# aq_mx_v1-6-0a.net
KiCad netlist of a schematic drawn in EAGLE
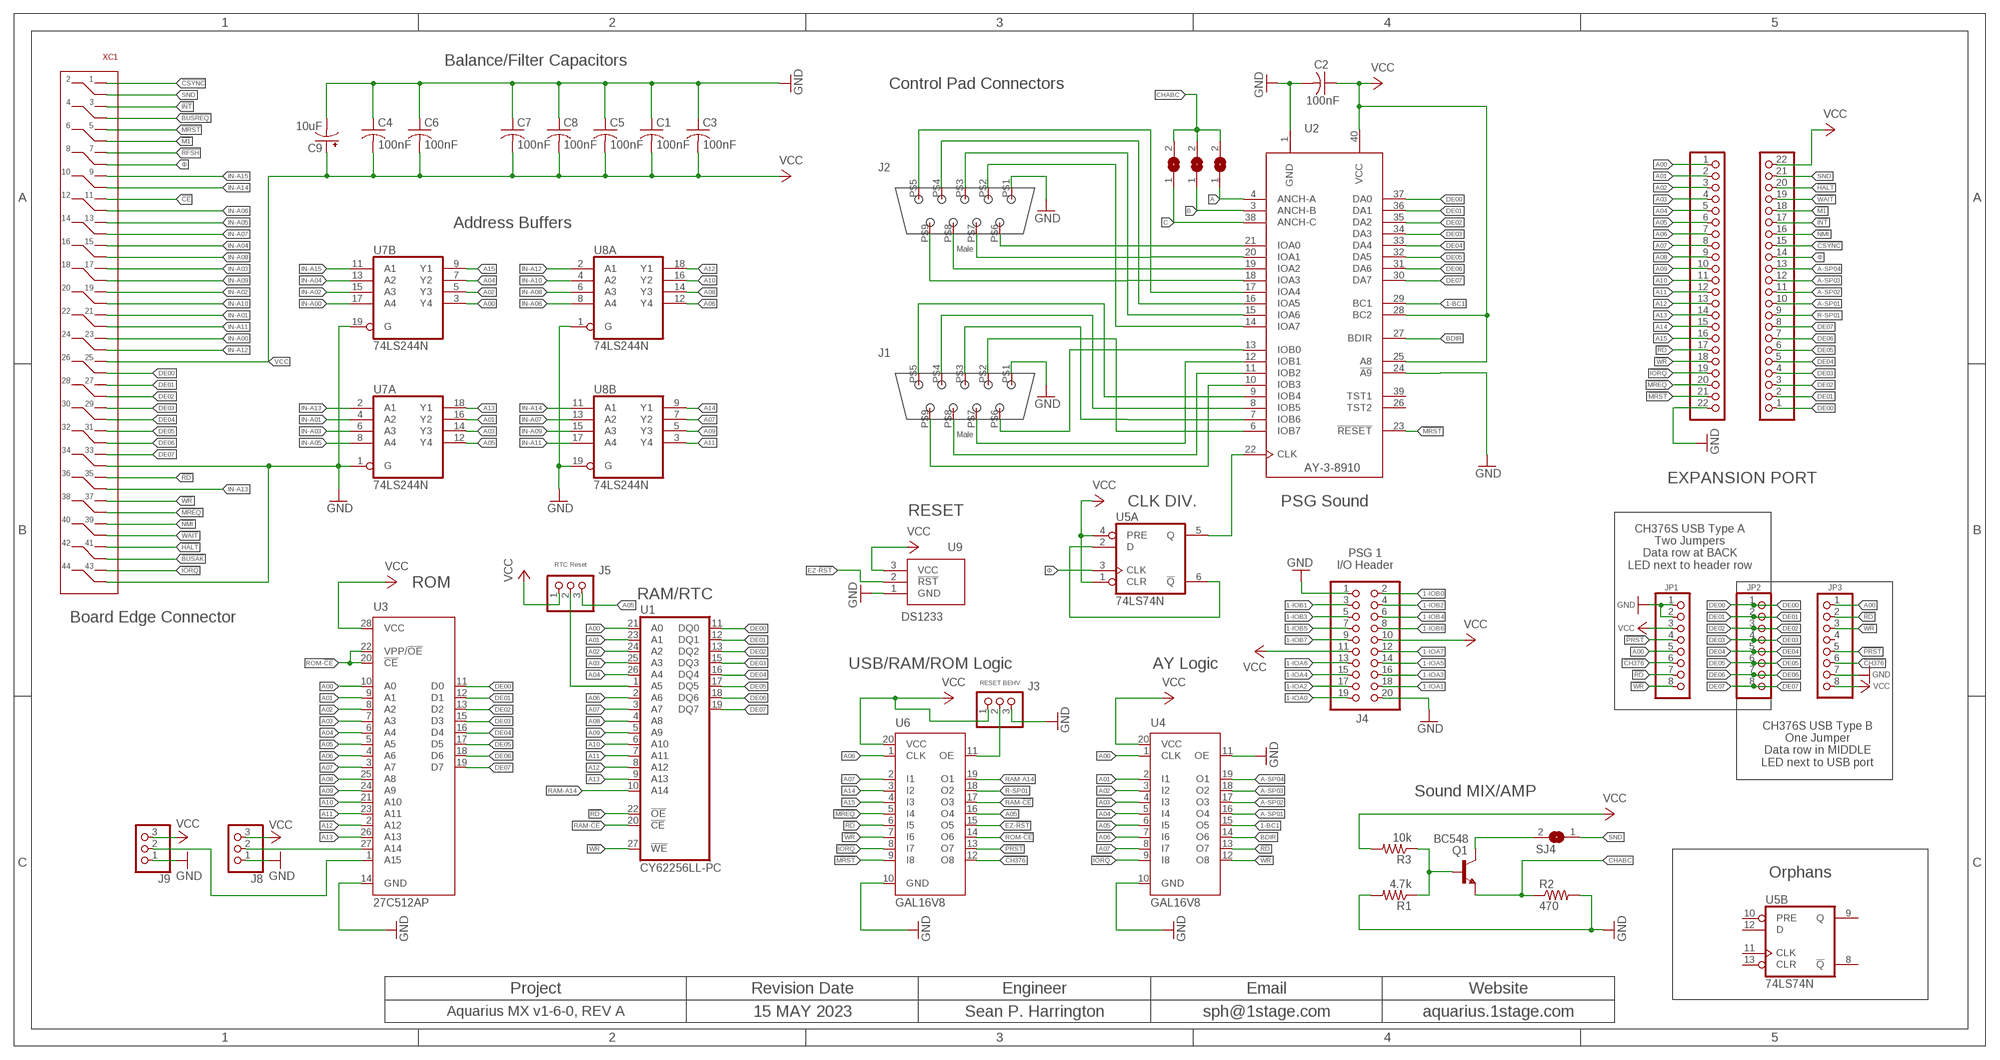
[diagram p0: schematic, sheet 1]

(export (version "E")
  (design (tool "Eeschema 10.0.6"))
  (components
    (comp (ref "C1")
      (value "100nF")
      (footprint "eagle-import:C050-025X075")
      (libsource (lib "eagle-import") (part "C-US050-025X075"))
    )
    (comp (ref "C2")
      (value "100nF")
      (footprint "eagle-import:C050-025X075")
      (libsource (lib "eagle-import") (part "C-US050-025X075"))
    )
    (comp (ref "C3")
      (value "100nF")
      (footprint "eagle-import:C050-025X075")
      (libsource (lib "eagle-import") (part "C-US050-025X075"))
    )
    (comp (ref "C4")
      (value "100nF")
      (footprint "eagle-import:C050-025X075")
      (libsource (lib "eagle-import") (part "C-US050-025X075"))
    )
    (comp (ref "C5")
      (value "100nF")
      (footprint "eagle-import:C050-025X075")
      (libsource (lib "eagle-import") (part "C-US050-025X075"))
    )
    (comp (ref "C6")
      (value "100nF")
      (footprint "eagle-import:C050-025X075")
      (libsource (lib "eagle-import") (part "C-US050-025X075"))
    )
    (comp (ref "C7")
      (value "100nF")
      (footprint "eagle-import:C050-025X075")
      (libsource (lib "eagle-import") (part "C-US050-025X075"))
    )
    (comp (ref "C8")
      (value "100nF")
      (footprint "eagle-import:C050-025X075")
      (libsource (lib "eagle-import") (part "C-US050-025X075"))
    )
    (comp (ref "C9")
      (value "10uF")
      (footprint "eagle-import:E22-6")
      (libsource (lib "eagle-import") (part "CPOL-USE22-6AXIAL"))
    )
    (comp (ref "J1")
      (value "DB9-MALE-RA")
      (footprint "eagle-import:DB9-MALE-RA")
      (libsource (lib "eagle-import") (part "DB9-MALE-RA"))
    )
    (comp (ref "J2")
      (value "DB9-MALE-RA")
      (footprint "eagle-import:DB9-MALE-RA")
      (libsource (lib "eagle-import") (part "DB9-MALE-RA"))
    )
    (comp (ref "J3")
      (value "RESET BEHV.")
      (footprint "eagle-import:1X03")
      (libsource (lib "eagle-import") (part "PINHD-1X3"))
    )
    (comp (ref "J4")
      (value "PINHD-2X10")
      (footprint "eagle-import:2X10")
      (libsource (lib "eagle-import") (part "PINHD-2X10"))
    )
    (comp (ref "J5")
      (value "RTC Reset")
      (footprint "eagle-import:1X03")
      (libsource (lib "eagle-import") (part "PINHD-1X3"))
    )
    (comp (ref "J6")
      (value "PINHD-1X22")
      (footprint "eagle-import:1X22")
      (libsource (lib "eagle-import") (part "PINHD-1X22"))
    )
    (comp (ref "J7")
      (value "PINHD-1X22")
      (footprint "eagle-import:1X22")
      (libsource (lib "eagle-import") (part "PINHD-1X22"))
    )
    (comp (ref "J8")
      (value "PINHD-1X3")
      (footprint "eagle-import:1X03")
      (libsource (lib "eagle-import") (part "PINHD-1X3"))
    )
    (comp (ref "J9")
      (value "PINHD-1X3")
      (footprint "eagle-import:1X03")
      (libsource (lib "eagle-import") (part "PINHD-1X3"))
    )
    (comp (ref "JP1")
      (value "PINHD-1X8")
      (footprint "eagle-import:1X08")
      (libsource (lib "eagle-import") (part "PINHD-1X8"))
    )
    (comp (ref "JP2")
      (value "PINHD-1X8")
      (footprint "eagle-import:1X08")
      (libsource (lib "eagle-import") (part "PINHD-1X8"))
    )
    (comp (ref "JP3")
      (value "PINHD-1X8")
      (footprint "eagle-import:1X08")
      (libsource (lib "eagle-import") (part "PINHD-1X8"))
    )
    (comp (ref "Q1")
      (value "BC548")
      (footprint "eagle-import:TO92-CBE")
      (libsource (lib "eagle-import") (part "-NPN-TO92-CBEBC548"))
    )
    (comp (ref "R1")
      (value "4.7k")
      (footprint "eagle-import:0204_7")
      (libsource (lib "eagle-import") (part "R-US_0204/7"))
    )
    (comp (ref "R2")
      (value "470")
      (footprint "eagle-import:0204_7")
      (libsource (lib "eagle-import") (part "R-US_0204/7"))
    )
    (comp (ref "R3")
      (value "10k")
      (footprint "eagle-import:0204_7")
      (libsource (lib "eagle-import") (part "R-US_0204/7"))
    )
    (comp (ref "SJ1") (value "SJ") (footprint "eagle-import:SJ") (libsource (lib "eagle-import") (part "SJ")))
    (comp (ref "SJ2") (value "SJ") (footprint "eagle-import:SJ") (libsource (lib "eagle-import") (part "SJ")))
    (comp (ref "SJ3") (value "SJ") (footprint "eagle-import:SJ") (libsource (lib "eagle-import") (part "SJ")))
    (comp (ref "SJ4") (value "SJ") (footprint "eagle-import:SJ") (libsource (lib "eagle-import") (part "SJ")))
    (comp (ref "U1")
      (value "CY62256LL-PC")
      (footprint "eagle-import:DIL28-6")
      (libsource (lib "eagle-import") (part "CY62256LL-?PC"))
    )
    (comp (ref "U2")
      (value "AY-3-8910")
      (footprint "eagle-import:RAD38910-DIL40-6")
      (libsource (lib "eagle-import") (part "RAD38910DIL40-6"))
    )
    (comp (ref "U3")
      (value "27C512AP")
      (footprint "eagle-import:DIL28-6")
      (fields (field (name "MPN") "M27C512-90B6"))
      (libsource (lib "eagle-import") (part "27512APC"))
    )
    (comp (ref "U4")
      (value "GAL16V8")
      (footprint "eagle-import:DIL20")
      (fields (field (name "MPN") "ATF16V8CZ-15PU"))
      (libsource (lib "eagle-import") (part "ATF16V8BP3"))
    )
    (comp (ref "U5")
      (value "74LS74N")
      (footprint "eagle-import:DIL14")
      (libsource (lib "eagle-import") (part "7474NLS"))
    )
    (comp (ref "U6")
      (value "GAL16V8")
      (footprint "eagle-import:DIL20")
      (fields (field (name "MPN") "ATF16V8CZ-15PU"))
      (libsource (lib "eagle-import") (part "ATF16V8BP3"))
    )
    (comp (ref "U7")
      (value "74LS244N")
      (footprint "eagle-import:DIL20")
      (libsource (lib "eagle-import") (part "74244NLS"))
    )
    (comp (ref "U8")
      (value "74LS244N")
      (footprint "eagle-import:DIL20")
      (libsource (lib "eagle-import") (part "74244NLS"))
    )
    (comp (ref "U9")
      (value "DS1233")
      (footprint "eagle-import:TO-92")
      (fields
        (field (name "ARROW_PART_NUMBER") "DS1233-10+")
        (field (name "MOUSER_PART_NUMBER") "700-DS1233-10")
      )
      (libsource (lib "eagle-import") (part "DS1233-10+"))
    )
    (comp (ref "XC1")
      (value "AQ-CART-EDGE")
      (footprint "eagle-import:AQ-CART-EDGE")
      (libsource (lib "eagle-import") (part "AQ-CART-EDGE"))
    )
  )
  (nets
    (net (code "1") (name "/EZ-~{RST}") (class "Default")
      (node (ref "U6") (pin "15") (pinfunction "O5_15") (pintype "output"))
      (node (ref "U9") (pin "2") (pinfunction "~{RST}_2") (pintype "input"))
    )
    (net (code "2") (name "/RAM-~{CE}") (class "Default")
      (node (ref "U1") (pin "20") (pinfunction "~{CE}_20") (pintype "input"))
      (node (ref "U6") (pin "17") (pinfunction "O3_17") (pintype "output"))
    )
    (net (code "3") (name "/ROM-~{CE}") (class "Default")
      (node (ref "U3") (pin "20") (pinfunction "~{CE}_20") (pintype "input"))
      (node (ref "U3") (pin "22") (pinfunction "VPP/~{OE}_22") (pintype "input"))
      (node (ref "U6") (pin "14") (pinfunction "O6_14") (pintype "output"))
    )
    (net (code "4") (name "/~{BUSAK}") (class "Default")
      (node (ref "XC1") (pin "P$42") (pinfunction "X42_P$42") (pintype "bidirectional"))
    )
    (net (code "5") (name "/~{BUSREQ}") (class "Default")
      (node (ref "XC1") (pin "P$4") (pinfunction "X4_P$4") (pintype "bidirectional"))
    )
    (net (code "6") (name "/~{CE}") (class "Default")
      (node (ref "XC1") (pin "P$11") (pinfunction "X11_P$11") (pintype "bidirectional"))
    )
    (net (code "7") (name "/~{CH376}") (class "Default")
      (node (ref "JP1") (pin "6") (pinfunction "6_6") (pintype "passive"))
      (node (ref "JP3") (pin "6") (pinfunction "6_6") (pintype "passive"))
      (node (ref "U6") (pin "12") (pinfunction "O8_12") (pintype "output"))
    )
    (net (code "8") (name "/~{CSYNC}") (class "Default")
      (node (ref "J6") (pin "15") (pinfunction "15_15") (pintype "passive"))
      (node (ref "XC1") (pin "P$1") (pinfunction "X1_P$1") (pintype "bidirectional"))
    )
    (net (code "9") (name "/~{HALT}") (class "Default")
      (node (ref "J6") (pin "20") (pinfunction "20_20") (pintype "passive"))
      (node (ref "XC1") (pin "P$41") (pinfunction "X41_P$41") (pintype "bidirectional"))
    )
    (net (code "10") (name "/~{INT}") (class "Default")
      (node (ref "J6") (pin "17") (pinfunction "17_17") (pintype "passive"))
      (node (ref "XC1") (pin "P$3") (pinfunction "X3_P$3") (pintype "bidirectional"))
    )
    (net (code "11") (name "/~{IORQ}") (class "Default")
      (node (ref "J7") (pin "19") (pinfunction "19_19") (pintype "passive"))
      (node (ref "U4") (pin "9") (pinfunction "I8_9") (pintype "input"))
      (node (ref "U6") (pin "8") (pinfunction "I7_8") (pintype "input"))
      (node (ref "XC1") (pin "P$43") (pinfunction "X43_P$43") (pintype "bidirectional"))
    )
    (net (code "12") (name "/~{M1}") (class "Default")
      (node (ref "J6") (pin "18") (pinfunction "18_18") (pintype "passive"))
      (node (ref "XC1") (pin "P$6") (pinfunction "X6_P$6") (pintype "bidirectional"))
    )
    (net (code "13") (name "/~{MREQ}") (class "Default")
      (node (ref "J7") (pin "20") (pinfunction "20_20") (pintype "passive"))
      (node (ref "U6") (pin "5") (pinfunction "I4_5") (pintype "input"))
      (node (ref "XC1") (pin "P$38") (pinfunction "X38_P$38") (pintype "bidirectional"))
    )
    (net (code "14") (name "/~{MRST}") (class "Default")
      (node (ref "J7") (pin "21") (pinfunction "21_21") (pintype "passive"))
      (node (ref "U2") (pin "23") (pinfunction "~{RESET}_23") (pintype "bidirectional"))
      (node (ref "U6") (pin "9") (pinfunction "I8_9") (pintype "input"))
      (node (ref "XC1") (pin "P$5") (pinfunction "X5_P$5") (pintype "bidirectional"))
    )
    (net (code "15") (name "/~{NMI}") (class "Default")
      (node (ref "J6") (pin "16") (pinfunction "16_16") (pintype "passive"))
      (node (ref "XC1") (pin "P$39") (pinfunction "X39_P$39") (pintype "bidirectional"))
    )
    (net (code "16") (name "/~{PRST}") (class "Default")
      (node (ref "JP1") (pin "4") (pinfunction "4_4") (pintype "passive"))
      (node (ref "JP3") (pin "5") (pinfunction "5_5") (pintype "passive"))
      (node (ref "U6") (pin "13") (pinfunction "O7_13") (pintype "output"))
    )
    (net (code "17") (name "/~{RD}") (class "Default")
      (node (ref "J7") (pin "17") (pinfunction "17_17") (pintype "passive"))
      (node (ref "JP1") (pin "7") (pinfunction "7_7") (pintype "passive"))
      (node (ref "JP3") (pin "2") (pinfunction "2_2") (pintype "passive"))
      (node (ref "U1") (pin "22") (pinfunction "~{OE}_22") (pintype "input"))
      (node (ref "U4") (pin "13") (pinfunction "O7_13") (pintype "output"))
      (node (ref "U6") (pin "6") (pinfunction "I5_6") (pintype "input"))
      (node (ref "XC1") (pin "P$35") (pinfunction "X35_P$35") (pintype "bidirectional"))
    )
    (net (code "18") (name "/~{RFSH}") (class "Default")
      (node (ref "XC1") (pin "P$7") (pinfunction "X7_P$7") (pintype "bidirectional"))
    )
    (net (code "19") (name "/~{WAIT}") (class "Default")
      (node (ref "J6") (pin "19") (pinfunction "19_19") (pintype "passive"))
      (node (ref "XC1") (pin "P$40") (pinfunction "X40_P$40") (pintype "bidirectional"))
    )
    (net (code "20") (name "/~{WR}") (class "Default")
      (node (ref "J7") (pin "18") (pinfunction "18_18") (pintype "passive"))
      (node (ref "JP1") (pin "8") (pinfunction "8_8") (pintype "passive"))
      (node (ref "JP3") (pin "3") (pinfunction "3_3") (pintype "passive"))
      (node (ref "U1") (pin "27") (pinfunction "~{WE}_27") (pintype "input"))
      (node (ref "U4") (pin "12") (pinfunction "O8_12") (pintype "output"))
      (node (ref "U6") (pin "7") (pinfunction "I6_7") (pintype "input"))
      (node (ref "XC1") (pin "P$37") (pinfunction "X37_P$37") (pintype "bidirectional"))
    )
    (net (code "21") (name "1-BC1") (class "Default")
      (node (ref "U2") (pin "29") (pinfunction "BC1_29") (pintype "bidirectional"))
      (node (ref "U4") (pin "15") (pinfunction "O5_15") (pintype "output"))
    )
    (net (code "22") (name "1-IOA0") (class "Default")
      (node (ref "J2") (pin "P$6") (pinfunction "P$6_P$6") (pintype "bidirectional"))
      (node (ref "J4") (pin "19") (pinfunction "19_19") (pintype "passive"))
      (node (ref "U2") (pin "21") (pinfunction "IOA0_21") (pintype "bidirectional"))
    )
    (net (code "23") (name "1-IOA1") (class "Default")
      (node (ref "J2") (pin "P$7") (pinfunction "P$7_P$7") (pintype "bidirectional"))
      (node (ref "J4") (pin "18") (pinfunction "18_18") (pintype "passive"))
      (node (ref "U2") (pin "20") (pinfunction "IOA1_20") (pintype "bidirectional"))
    )
    (net (code "24") (name "1-IOA2") (class "Default")
      (node (ref "J2") (pin "P$8") (pinfunction "P$8_P$8") (pintype "bidirectional"))
      (node (ref "J4") (pin "17") (pinfunction "17_17") (pintype "passive"))
      (node (ref "U2") (pin "19") (pinfunction "IOA2_19") (pintype "bidirectional"))
    )
    (net (code "25") (name "1-IOA3") (class "Default")
      (node (ref "J2") (pin "P$9") (pinfunction "P$9_P$9") (pintype "bidirectional"))
      (node (ref "J4") (pin "16") (pinfunction "16_16") (pintype "passive"))
      (node (ref "U2") (pin "18") (pinfunction "IOA3_18") (pintype "bidirectional"))
    )
    (net (code "26") (name "1-IOA4") (class "Default")
      (node (ref "J2") (pin "P$5") (pinfunction "P$5_P$5") (pintype "bidirectional"))
      (node (ref "J4") (pin "15") (pinfunction "15_15") (pintype "passive"))
      (node (ref "U2") (pin "17") (pinfunction "IOA4_17") (pintype "bidirectional"))
    )
    (net (code "27") (name "1-IOA5") (class "Default")
      (node (ref "J2") (pin "P$4") (pinfunction "P$4_P$4") (pintype "bidirectional"))
      (node (ref "J4") (pin "14") (pinfunction "14_14") (pintype "passive"))
      (node (ref "U2") (pin "16") (pinfunction "IOA5_16") (pintype "bidirectional"))
    )
    (net (code "28") (name "1-IOA6") (class "Default")
      (node (ref "J2") (pin "P$3") (pinfunction "P$3_P$3") (pintype "bidirectional"))
      (node (ref "J4") (pin "13") (pinfunction "13_13") (pintype "passive"))
      (node (ref "U2") (pin "15") (pinfunction "IOA6_15") (pintype "bidirectional"))
    )
    (net (code "29") (name "1-IOA7") (class "Default")
      (node (ref "J2") (pin "P$2") (pinfunction "P$2_P$2") (pintype "bidirectional"))
      (node (ref "J4") (pin "12") (pinfunction "12_12") (pintype "passive"))
      (node (ref "U2") (pin "14") (pinfunction "IOA7_14") (pintype "bidirectional"))
    )
    (net (code "30") (name "1-IOB0") (class "Default")
      (node (ref "J1") (pin "P$6") (pinfunction "P$6_P$6") (pintype "bidirectional"))
      (node (ref "J4") (pin "2") (pinfunction "2_2") (pintype "passive"))
      (node (ref "U2") (pin "13") (pinfunction "IOB0_13") (pintype "bidirectional"))
    )
    (net (code "31") (name "1-IOB1") (class "Default")
      (node (ref "J1") (pin "P$7") (pinfunction "P$7_P$7") (pintype "bidirectional"))
      (node (ref "J4") (pin "3") (pinfunction "3_3") (pintype "passive"))
      (node (ref "U2") (pin "12") (pinfunction "IOB1_12") (pintype "bidirectional"))
    )
    (net (code "32") (name "1-IOB2") (class "Default")
      (node (ref "J1") (pin "P$8") (pinfunction "P$8_P$8") (pintype "bidirectional"))
      (node (ref "J4") (pin "4") (pinfunction "4_4") (pintype "passive"))
      (node (ref "U2") (pin "11") (pinfunction "IOB2_11") (pintype "bidirectional"))
    )
    (net (code "33") (name "1-IOB3") (class "Default")
      (node (ref "J1") (pin "P$9") (pinfunction "P$9_P$9") (pintype "bidirectional"))
      (node (ref "J4") (pin "5") (pinfunction "5_5") (pintype "passive"))
      (node (ref "U2") (pin "10") (pinfunction "IOB3_10") (pintype "bidirectional"))
    )
    (net (code "34") (name "1-IOB4") (class "Default")
      (node (ref "J1") (pin "P$5") (pinfunction "P$5_P$5") (pintype "bidirectional"))
      (node (ref "J4") (pin "6") (pinfunction "6_6") (pintype "passive"))
      (node (ref "U2") (pin "9") (pinfunction "IOB4_9") (pintype "bidirectional"))
    )
    (net (code "35") (name "1-IOB5") (class "Default")
      (node (ref "J1") (pin "P$4") (pinfunction "P$4_P$4") (pintype "bidirectional"))
      (node (ref "J4") (pin "7") (pinfunction "7_7") (pintype "passive"))
      (node (ref "U2") (pin "8") (pinfunction "IOB5_8") (pintype "bidirectional"))
    )
    (net (code "36") (name "1-IOB6") (class "Default")
      (node (ref "J1") (pin "P$3") (pinfunction "P$3_P$3") (pintype "bidirectional"))
      (node (ref "J4") (pin "8") (pinfunction "8_8") (pintype "passive"))
      (node (ref "U2") (pin "7") (pinfunction "IOB6_7") (pintype "bidirectional"))
    )
    (net (code "37") (name "1-IOB7") (class "Default")
      (node (ref "J1") (pin "P$2") (pinfunction "P$2_P$2") (pintype "bidirectional"))
      (node (ref "J4") (pin "9") (pinfunction "9_9") (pintype "passive"))
      (node (ref "U2") (pin "6") (pinfunction "IOB7_6") (pintype "bidirectional"))
    )
    (net (code "38") (name "A") (class "Default")
      (node (ref "SJ1") (pin "1") (pinfunction "1_1") (pintype "passive"))
      (node (ref "U2") (pin "4") (pinfunction "ANCH-A_4") (pintype "bidirectional"))
    )
    (net (code "39") (name "A-SP01") (class "Default")
      (node (ref "J6") (pin "10") (pinfunction "10_10") (pintype "passive"))
      (node (ref "U4") (pin "16") (pinfunction "O4_16") (pintype "output"))
    )
    (net (code "40") (name "A-SP02") (class "Default")
      (node (ref "J6") (pin "11") (pinfunction "11_11") (pintype "passive"))
      (node (ref "U4") (pin "17") (pinfunction "O3_17") (pintype "output"))
    )
    (net (code "41") (name "A-SP03") (class "Default")
      (node (ref "J6") (pin "12") (pinfunction "12_12") (pintype "passive"))
      (node (ref "U4") (pin "18") (pinfunction "O2_18") (pintype "output"))
    )
    (net (code "42") (name "A-SP04") (class "Default")
      (node (ref "J6") (pin "13") (pinfunction "13_13") (pintype "passive"))
      (node (ref "U4") (pin "19") (pinfunction "O1_19") (pintype "output"))
    )
    (net (code "43") (name "A00") (class "Default")
      (node (ref "J7") (pin "1") (pinfunction "1_1") (pintype "passive"))
      (node (ref "JP1") (pin "5") (pinfunction "5_5") (pintype "passive"))
      (node (ref "JP3") (pin "1") (pinfunction "1_1") (pintype "passive"))
      (node (ref "U1") (pin "21") (pinfunction "A0_21") (pintype "input"))
      (node (ref "U3") (pin "10") (pinfunction "A0_10") (pintype "input"))
      (node (ref "U4") (pin "1") (pinfunction "CLK_1") (pintype "input"))
      (node (ref "U7") (pin "3") (pinfunction "Y4_3") (pintype "tri_state"))
    )
    (net (code "44") (name "A01") (class "Default")
      (node (ref "J7") (pin "2") (pinfunction "2_2") (pintype "passive"))
      (node (ref "U1") (pin "23") (pinfunction "A1_23") (pintype "input"))
      (node (ref "U3") (pin "9") (pinfunction "A1_9") (pintype "input"))
      (node (ref "U4") (pin "2") (pinfunction "I1_2") (pintype "input"))
      (node (ref "U7") (pin "16") (pinfunction "Y2_16") (pintype "tri_state"))
    )
    (net (code "45") (name "A02") (class "Default")
      (node (ref "J7") (pin "3") (pinfunction "3_3") (pintype "passive"))
      (node (ref "U1") (pin "24") (pinfunction "A2_24") (pintype "input"))
      (node (ref "U3") (pin "8") (pinfunction "A2_8") (pintype "input"))
      (node (ref "U4") (pin "3") (pinfunction "I2_3") (pintype "input"))
      (node (ref "U7") (pin "5") (pinfunction "Y3_5") (pintype "tri_state"))
    )
    (net (code "46") (name "A03") (class "Default")
      (node (ref "J7") (pin "4") (pinfunction "4_4") (pintype "passive"))
      (node (ref "U1") (pin "25") (pinfunction "A3_25") (pintype "input"))
      (node (ref "U3") (pin "7") (pinfunction "A3_7") (pintype "input"))
      (node (ref "U4") (pin "4") (pinfunction "I3_4") (pintype "input"))
      (node (ref "U7") (pin "14") (pinfunction "Y3_14") (pintype "tri_state"))
    )
    (net (code "47") (name "A04") (class "Default")
      (node (ref "J7") (pin "5") (pinfunction "5_5") (pintype "passive"))
      (node (ref "U1") (pin "26") (pinfunction "A4_26") (pintype "input"))
      (node (ref "U3") (pin "6") (pinfunction "A4_6") (pintype "input"))
      (node (ref "U4") (pin "5") (pinfunction "I4_5") (pintype "input"))
      (node (ref "U7") (pin "7") (pinfunction "Y2_7") (pintype "tri_state"))
    )
    (net (code "48") (name "A05") (class "Default")
      (node (ref "J5") (pin "3") (pinfunction "3_3") (pintype "passive"))
      (node (ref "J7") (pin "6") (pinfunction "6_6") (pintype "passive"))
      (node (ref "U3") (pin "5") (pinfunction "A5_5") (pintype "input"))
      (node (ref "U4") (pin "6") (pinfunction "I5_6") (pintype "input"))
      (node (ref "U6") (pin "16") (pinfunction "O4_16") (pintype "output"))
      (node (ref "U7") (pin "12") (pinfunction "Y4_12") (pintype "tri_state"))
    )
    (net (code "49") (name "A06") (class "Default")
      (node (ref "J7") (pin "7") (pinfunction "7_7") (pintype "passive"))
      (node (ref "U1") (pin "2") (pinfunction "A6_2") (pintype "input"))
      (node (ref "U3") (pin "4") (pinfunction "A6_4") (pintype "input"))
      (node (ref "U4") (pin "7") (pinfunction "I6_7") (pintype "input"))
      (node (ref "U6") (pin "1") (pinfunction "CLK_1") (pintype "input"))
      (node (ref "U8") (pin "12") (pinfunction "Y4_12") (pintype "tri_state"))
    )
    (net (code "50") (name "A07") (class "Default")
      (node (ref "J7") (pin "8") (pinfunction "8_8") (pintype "passive"))
      (node (ref "U1") (pin "3") (pinfunction "A7_3") (pintype "input"))
      (node (ref "U3") (pin "3") (pinfunction "A7_3") (pintype "input"))
      (node (ref "U4") (pin "8") (pinfunction "I7_8") (pintype "input"))
      (node (ref "U6") (pin "2") (pinfunction "I1_2") (pintype "input"))
      (node (ref "U8") (pin "7") (pinfunction "Y2_7") (pintype "tri_state"))
    )
    (net (code "51") (name "A08") (class "Default")
      (node (ref "J7") (pin "9") (pinfunction "9_9") (pintype "passive"))
      (node (ref "U1") (pin "4") (pinfunction "A8_4") (pintype "input"))
      (node (ref "U3") (pin "25") (pinfunction "A8_25") (pintype "input"))
      (node (ref "U8") (pin "14") (pinfunction "Y3_14") (pintype "tri_state"))
    )
    (net (code "52") (name "A09") (class "Default")
      (node (ref "J7") (pin "10") (pinfunction "10_10") (pintype "passive"))
      (node (ref "U1") (pin "5") (pinfunction "A9_5") (pintype "input"))
      (node (ref "U3") (pin "24") (pinfunction "A9_24") (pintype "input"))
      (node (ref "U8") (pin "5") (pinfunction "Y3_5") (pintype "tri_state"))
    )
    (net (code "53") (name "A10") (class "Default")
      (node (ref "J7") (pin "11") (pinfunction "11_11") (pintype "passive"))
      (node (ref "U1") (pin "6") (pinfunction "A10_6") (pintype "input"))
      (node (ref "U3") (pin "21") (pinfunction "A10_21") (pintype "input"))
      (node (ref "U8") (pin "16") (pinfunction "Y2_16") (pintype "tri_state"))
    )
    (net (code "54") (name "A11") (class "Default")
      (node (ref "J7") (pin "12") (pinfunction "12_12") (pintype "passive"))
      (node (ref "U1") (pin "7") (pinfunction "A11_7") (pintype "input"))
      (node (ref "U3") (pin "23") (pinfunction "A11_23") (pintype "input"))
      (node (ref "U8") (pin "3") (pinfunction "Y4_3") (pintype "tri_state"))
    )
    (net (code "55") (name "A12") (class "Default")
      (node (ref "J7") (pin "13") (pinfunction "13_13") (pintype "passive"))
      (node (ref "U1") (pin "8") (pinfunction "A12_8") (pintype "input"))
      (node (ref "U3") (pin "2") (pinfunction "A12_2") (pintype "input"))
      (node (ref "U8") (pin "18") (pinfunction "Y1_18") (pintype "tri_state"))
    )
    (net (code "56") (name "A13") (class "Default")
      (node (ref "J7") (pin "14") (pinfunction "14_14") (pintype "passive"))
      (node (ref "U1") (pin "9") (pinfunction "A13_9") (pintype "input"))
      (node (ref "U3") (pin "26") (pinfunction "A13_26") (pintype "input"))
      (node (ref "U7") (pin "18") (pinfunction "Y1_18") (pintype "tri_state"))
    )
    (net (code "57") (name "A14") (class "Default")
      (node (ref "J7") (pin "15") (pinfunction "15_15") (pintype "passive"))
      (node (ref "U6") (pin "3") (pinfunction "I2_3") (pintype "input"))
      (node (ref "U8") (pin "9") (pinfunction "Y1_9") (pintype "tri_state"))
    )
    (net (code "58") (name "A15") (class "Default")
      (node (ref "J7") (pin "16") (pinfunction "16_16") (pintype "passive"))
      (node (ref "U6") (pin "4") (pinfunction "I3_4") (pintype "input"))
      (node (ref "U7") (pin "9") (pinfunction "Y1_9") (pintype "tri_state"))
    )
    (net (code "59") (name "B") (class "Default")
      (node (ref "SJ2") (pin "1") (pinfunction "1_1") (pintype "passive"))
      (node (ref "U2") (pin "3") (pinfunction "ANCH-B_3") (pintype "bidirectional"))
    )
    (net (code "60") (name "BDIR") (class "Default")
      (node (ref "U2") (pin "27") (pinfunction "BDIR_27") (pintype "bidirectional"))
      (node (ref "U4") (pin "14") (pinfunction "O6_14") (pintype "output"))
    )
    (net (code "61") (name "C") (class "Default")
      (node (ref "SJ3") (pin "1") (pinfunction "1_1") (pintype "passive"))
      (node (ref "U2") (pin "38") (pinfunction "ANCH-C_38") (pintype "bidirectional"))
    )
    (net (code "62") (name "CHABC") (class "Default")
      (node (ref "Q1") (pin "E") (pinfunction "E_E") (pintype "passive"))
      (node (ref "R2") (pin "1") (pinfunction "1_1") (pintype "passive"))
      (node (ref "SJ1") (pin "2") (pinfunction "2_2") (pintype "passive"))
      (node (ref "SJ2") (pin "2") (pinfunction "2_2") (pintype "passive"))
      (node (ref "SJ3") (pin "2") (pinfunction "2_2") (pintype "passive"))
    )
    (net (code "63") (name "DE00") (class "Default")
      (node (ref "J6") (pin "1") (pinfunction "1_1") (pintype "passive"))
      (node (ref "JP2") (pin "1") (pinfunction "1_1") (pintype "passive"))
      (node (ref "U1") (pin "11") (pinfunction "DQ0_11") (pintype "bidirectional"))
      (node (ref "U2") (pin "37") (pinfunction "DA0_37") (pintype "bidirectional"))
      (node (ref "U3") (pin "11") (pinfunction "D0_11") (pintype "tri_state"))
      (node (ref "XC1") (pin "P$26") (pinfunction "X26_P$26") (pintype "bidirectional"))
    )
    (net (code "64") (name "DE01") (class "Default")
      (node (ref "J6") (pin "2") (pinfunction "2_2") (pintype "passive"))
      (node (ref "JP2") (pin "2") (pinfunction "2_2") (pintype "passive"))
      (node (ref "U1") (pin "12") (pinfunction "DQ1_12") (pintype "bidirectional"))
      (node (ref "U2") (pin "36") (pinfunction "DA1_36") (pintype "bidirectional"))
      (node (ref "U3") (pin "12") (pinfunction "D1_12") (pintype "tri_state"))
      (node (ref "XC1") (pin "P$27") (pinfunction "X27_P$27") (pintype "bidirectional"))
    )
    (net (code "65") (name "DE02") (class "Default")
      (node (ref "J6") (pin "3") (pinfunction "3_3") (pintype "passive"))
      (node (ref "JP2") (pin "3") (pinfunction "3_3") (pintype "passive"))
      (node (ref "U1") (pin "13") (pinfunction "DQ2_13") (pintype "bidirectional"))
      (node (ref "U2") (pin "35") (pinfunction "DA2_35") (pintype "bidirectional"))
      (node (ref "U3") (pin "13") (pinfunction "D2_13") (pintype "tri_state"))
      (node (ref "XC1") (pin "P$28") (pinfunction "X28_P$28") (pintype "bidirectional"))
    )
    (net (code "66") (name "DE03") (class "Default")
      (node (ref "J6") (pin "4") (pinfunction "4_4") (pintype "passive"))
      (node (ref "JP2") (pin "4") (pinfunction "4_4") (pintype "passive"))
      (node (ref "U1") (pin "15") (pinfunction "DQ3_15") (pintype "bidirectional"))
      (node (ref "U2") (pin "34") (pinfunction "DA3_34") (pintype "bidirectional"))
      (node (ref "U3") (pin "15") (pinfunction "D3_15") (pintype "tri_state"))
      (node (ref "XC1") (pin "P$29") (pinfunction "X29_P$29") (pintype "bidirectional"))
    )
    (net (code "67") (name "DE04") (class "Default")
      (node (ref "J6") (pin "5") (pinfunction "5_5") (pintype "passive"))
      (node (ref "JP2") (pin "5") (pinfunction "5_5") (pintype "passive"))
      (node (ref "U1") (pin "16") (pinfunction "DQ4_16") (pintype "bidirectional"))
      (node (ref "U2") (pin "33") (pinfunction "DA4_33") (pintype "bidirectional"))
      (node (ref "U3") (pin "16") (pinfunction "D4_16") (pintype "tri_state"))
      (node (ref "XC1") (pin "P$30") (pinfunction "X30_P$30") (pintype "bidirectional"))
    )
    (net (code "68") (name "DE05") (class "Default")
      (node (ref "J6") (pin "6") (pinfunction "6_6") (pintype "passive"))
      (node (ref "JP2") (pin "6") (pinfunction "6_6") (pintype "passive"))
      (node (ref "U1") (pin "17") (pinfunction "DQ5_17") (pintype "bidirectional"))
      (node (ref "U2") (pin "32") (pinfunction "DA5_32") (pintype "bidirectional"))
      (node (ref "U3") (pin "17") (pinfunction "D5_17") (pintype "tri_state"))
      (node (ref "XC1") (pin "P$31") (pinfunction "X31_P$31") (pintype "bidirectional"))
    )
    (net (code "69") (name "DE06") (class "Default")
      (node (ref "J6") (pin "7") (pinfunction "7_7") (pintype "passive"))
      (node (ref "JP2") (pin "7") (pinfunction "7_7") (pintype "passive"))
      (node (ref "U1") (pin "18") (pinfunction "DQ6_18") (pintype "bidirectional"))
      (node (ref "U2") (pin "31") (pinfunction "DA6_31") (pintype "bidirectional"))
      (node (ref "U3") (pin "18") (pinfunction "D6_18") (pintype "tri_state"))
      (node (ref "XC1") (pin "P$32") (pinfunction "X32_P$32") (pintype "bidirectional"))
    )
    (net (code "70") (name "DE07") (class "Default")
      (node (ref "J6") (pin "8") (pinfunction "8_8") (pintype "passive"))
      (node (ref "JP2") (pin "8") (pinfunction "8_8") (pintype "passive"))
      (node (ref "U1") (pin "19") (pinfunction "DQ7_19") (pintype "bidirectional"))
      (node (ref "U2") (pin "30") (pinfunction "DA7_30") (pintype "bidirectional"))
      (node (ref "U3") (pin "19") (pinfunction "D7_19") (pintype "tri_state"))
      (node (ref "XC1") (pin "P$33") (pinfunction "X33_P$33") (pintype "bidirectional"))
    )
    (net (code "71") (name "GND") (class "Default")
      (node (ref "C1") (pin "1") (pinfunction "1_1") (pintype "passive"))
      (node (ref "C2") (pin "2") (pinfunction "2_2") (pintype "passive"))
      (node (ref "C3") (pin "1") (pinfunction "1_1") (pintype "passive"))
      (node (ref "C4") (pin "1") (pinfunction "1_1") (pintype "passive"))
      (node (ref "C5") (pin "1") (pinfunction "1_1") (pintype "passive"))
      (node (ref "C6") (pin "1") (pinfunction "1_1") (pintype "passive"))
      (node (ref "C7") (pin "1") (pinfunction "1_1") (pintype "passive"))
      (node (ref "C8") (pin "1") (pinfunction "1_1") (pintype "passive"))
      (node (ref "C9") (pin "-") (pinfunction "-_-") (pintype "passive"))
      (node (ref "J1") (pin "P$1") (pinfunction "P$1_P$1") (pintype "bidirectional"))
      (node (ref "J2") (pin "P$1") (pinfunction "P$1_P$1") (pintype "bidirectional"))
      (node (ref "J3") (pin "3") (pinfunction "3_3") (pintype "passive"))
      (node (ref "J4") (pin "1") (pinfunction "1_1") (pintype "passive"))
      (node (ref "J4") (pin "20") (pinfunction "20_20") (pintype "passive"))
      (node (ref "J7") (pin "22") (pinfunction "22_22") (pintype "passive"))
      (node (ref "J8") (pin "1") (pinfunction "1_1") (pintype "passive"))
      (node (ref "J9") (pin "1") (pinfunction "1_1") (pintype "passive"))
      (node (ref "JP1") (pin "1") (pinfunction "1_1") (pintype "passive"))
      (node (ref "JP1") (pin "2") (pinfunction "2_2") (pintype "passive"))
      (node (ref "JP3") (pin "7") (pinfunction "7_7") (pintype "passive"))
      (node (ref "R1") (pin "2") (pinfunction "2_2") (pintype "passive"))
      (node (ref "R2") (pin "2") (pinfunction "2_2") (pintype "passive"))
      (node (ref "U2") (pin "1") (pinfunction "GND_1") (pintype "power_in"))
      (node (ref "U2") (pin "24") (pinfunction "~{A9}_24") (pintype "bidirectional"))
      (node (ref "U3") (pin "14") (pinfunction "GND_14") (pintype "power_in"))
      (node (ref "U4") (pin "10") (pinfunction "GND_10") (pintype "power_in"))
      (node (ref "U4") (pin "11") (pinfunction "OE_11") (pintype "input"))
      (node (ref "U6") (pin "10") (pinfunction "GND_10") (pintype "power_in"))
      (node (ref "U7") (pin "1") (pinfunction "G_1") (pintype "input"))
      (node (ref "U7") (pin "19") (pinfunction "G_19") (pintype "input"))
      (node (ref "U8") (pin "1") (pinfunction "G_1") (pintype "input"))
      (node (ref "U8") (pin "19") (pinfunction "G_19") (pintype "input"))
      (node (ref "U9") (pin "1") (pinfunction "GND_1") (pintype "power_in"))
      (node (ref "XC1") (pin "P$34") (pinfunction "X34_P$34") (pintype "bidirectional"))
      (node (ref "XC1") (pin "P$44") (pinfunction "X44_P$44") (pintype "bidirectional"))
    )
    (net (code "72") (name "IN-A00") (class "Default")
      (node (ref "U7") (pin "17") (pinfunction "A4_17") (pintype "input"))
      (node (ref "XC1") (pin "P$23") (pinfunction "X23_P$23") (pintype "bidirectional"))
    )
    (net (code "73") (name "IN-A01") (class "Default")
      (node (ref "U7") (pin "4") (pinfunction "A2_4") (pintype "input"))
      (node (ref "XC1") (pin "P$21") (pinfunction "X21_P$21") (pintype "bidirectional"))
    )
    (net (code "74") (name "IN-A02") (class "Default")
      (node (ref "U7") (pin "15") (pinfunction "A3_15") (pintype "input"))
      (node (ref "XC1") (pin "P$19") (pinfunction "X19_P$19") (pintype "bidirectional"))
    )
    (net (code "75") (name "IN-A03") (class "Default")
      (node (ref "U7") (pin "6") (pinfunction "A3_6") (pintype "input"))
      (node (ref "XC1") (pin "P$17") (pinfunction "X17_P$17") (pintype "bidirectional"))
    )
    (net (code "76") (name "IN-A04") (class "Default")
      (node (ref "U7") (pin "13") (pinfunction "A2_13") (pintype "input"))
      (node (ref "XC1") (pin "P$15") (pinfunction "X15_P$15") (pintype "bidirectional"))
    )
    (net (code "77") (name "IN-A05") (class "Default")
      (node (ref "U7") (pin "8") (pinfunction "A4_8") (pintype "input"))
      (node (ref "XC1") (pin "P$13") (pinfunction "X13_P$13") (pintype "bidirectional"))
    )
    (net (code "78") (name "IN-A06") (class "Default")
      (node (ref "U8") (pin "8") (pinfunction "A4_8") (pintype "input"))
      (node (ref "XC1") (pin "P$12") (pinfunction "X12_P$12") (pintype "bidirectional"))
    )
    (net (code "79") (name "IN-A07") (class "Default")
      (node (ref "U8") (pin "13") (pinfunction "A2_13") (pintype "input"))
      (node (ref "XC1") (pin "P$14") (pinfunction "X14_P$14") (pintype "bidirectional"))
    )
    (net (code "80") (name "IN-A08") (class "Default")
      (node (ref "U8") (pin "6") (pinfunction "A3_6") (pintype "input"))
      (node (ref "XC1") (pin "P$16") (pinfunction "X16_P$16") (pintype "bidirectional"))
    )
    (net (code "81") (name "IN-A09") (class "Default")
      (node (ref "U8") (pin "15") (pinfunction "A3_15") (pintype "input"))
      (node (ref "XC1") (pin "P$18") (pinfunction "X18_P$18") (pintype "bidirectional"))
    )
    (net (code "82") (name "IN-A10") (class "Default")
      (node (ref "U8") (pin "4") (pinfunction "A2_4") (pintype "input"))
      (node (ref "XC1") (pin "P$20") (pinfunction "X20_P$20") (pintype "bidirectional"))
    )
    (net (code "83") (name "IN-A11") (class "Default")
      (node (ref "U8") (pin "17") (pinfunction "A4_17") (pintype "input"))
      (node (ref "XC1") (pin "P$22") (pinfunction "X22_P$22") (pintype "bidirectional"))
    )
    (net (code "84") (name "IN-A12") (class "Default")
      (node (ref "U8") (pin "2") (pinfunction "A1_2") (pintype "input"))
      (node (ref "XC1") (pin "P$24") (pinfunction "X24_P$24") (pintype "bidirectional"))
    )
    (net (code "85") (name "IN-A13") (class "Default")
      (node (ref "U7") (pin "2") (pinfunction "A1_2") (pintype "input"))
      (node (ref "XC1") (pin "P$36") (pinfunction "X36_P$36") (pintype "bidirectional"))
    )
    (net (code "86") (name "IN-A14") (class "Default")
      (node (ref "U8") (pin "11") (pinfunction "A1_11") (pintype "input"))
      (node (ref "XC1") (pin "P$10") (pinfunction "X10_P$10") (pintype "bidirectional"))
    )
    (net (code "87") (name "IN-A15") (class "Default")
      (node (ref "U7") (pin "11") (pinfunction "A1_11") (pintype "input"))
      (node (ref "XC1") (pin "P$9") (pinfunction "X9_P$9") (pintype "bidirectional"))
    )
    (net (code "88") (name "Net-(Q1-PadB)") (class "Default")
      (node (ref "Q1") (pin "B") (pinfunction "B_B") (pintype "passive"))
      (node (ref "R1") (pin "1") (pinfunction "1_1") (pintype "passive"))
      (node (ref "R3") (pin "1") (pinfunction "1_1") (pintype "passive"))
    )
    (net (code "89") (name "Net-(Q1-PadC)") (class "Default")
      (node (ref "Q1") (pin "C") (pinfunction "C_C") (pintype "passive"))
      (node (ref "SJ4") (pin "2") (pinfunction "2_2") (pintype "passive"))
    )
    (net (code "90") (name "Net-(U1A-A5)") (class "Default")
      (node (ref "J5") (pin "2") (pinfunction "2_2") (pintype "passive"))
      (node (ref "U1") (pin "1") (pinfunction "A5_1") (pintype "input"))
    )
    (net (code "91") (name "Net-(U2-CLK)") (class "Default")
      (node (ref "U2") (pin "22") (pinfunction "CLK_22") (pintype "input"))
      (node (ref "U5") (pin "5") (pinfunction "Q_5") (pintype "output"))
    )
    (net (code "92") (name "Net-(U3-A14)") (class "Default")
      (node (ref "J8") (pin "2") (pinfunction "2_2") (pintype "passive"))
      (node (ref "U3") (pin "27") (pinfunction "A14_27") (pintype "input"))
    )
    (net (code "93") (name "Net-(U3-A15)") (class "Default")
      (node (ref "J9") (pin "2") (pinfunction "2_2") (pintype "passive"))
      (node (ref "U3") (pin "1") (pinfunction "A15_1") (pintype "input"))
    )
    (net (code "94") (name "Net-(U5A-D)") (class "Default")
      (node (ref "U5") (pin "2") (pinfunction "D_2") (pintype "input"))
      (node (ref "U5") (pin "6") (pinfunction "~{Q}_6") (pintype "output"))
    )
    (net (code "95") (name "Net-(U6-OE)") (class "Default")
      (node (ref "J3") (pin "2") (pinfunction "2_2") (pintype "passive"))
      (node (ref "U6") (pin "11") (pinfunction "OE_11") (pintype "input"))
    )
    (net (code "96") (name "R-SP01") (class "Default")
      (node (ref "J6") (pin "9") (pinfunction "9_9") (pintype "passive"))
      (node (ref "U6") (pin "18") (pinfunction "O2_18") (pintype "output"))
    )
    (net (code "97") (name "RAM-A14") (class "Default")
      (node (ref "U1") (pin "10") (pinfunction "A14_10") (pintype "input"))
      (node (ref "U6") (pin "19") (pinfunction "O1_19") (pintype "output"))
    )
    (net (code "98") (name "SND") (class "Default")
      (node (ref "J6") (pin "21") (pinfunction "21_21") (pintype "passive"))
      (node (ref "SJ4") (pin "1") (pinfunction "1_1") (pintype "passive"))
      (node (ref "XC1") (pin "P$2") (pinfunction "X2_P$2") (pintype "bidirectional"))
    )
    (net (code "99") (name "VCC") (class "Default")
      (node (ref "C1") (pin "2") (pinfunction "2_2") (pintype "passive"))
      (node (ref "C2") (pin "1") (pinfunction "1_1") (pintype "passive"))
      (node (ref "C3") (pin "2") (pinfunction "2_2") (pintype "passive"))
      (node (ref "C4") (pin "2") (pinfunction "2_2") (pintype "passive"))
      (node (ref "C5") (pin "2") (pinfunction "2_2") (pintype "passive"))
      (node (ref "C6") (pin "2") (pinfunction "2_2") (pintype "passive"))
      (node (ref "C7") (pin "2") (pinfunction "2_2") (pintype "passive"))
      (node (ref "C8") (pin "2") (pinfunction "2_2") (pintype "passive"))
      (node (ref "C9") (pin "+") (pinfunction "+_+") (pintype "passive"))
      (node (ref "J3") (pin "1") (pinfunction "1_1") (pintype "passive"))
      (node (ref "J4") (pin "10") (pinfunction "10_10") (pintype "passive"))
      (node (ref "J4") (pin "11") (pinfunction "11_11") (pintype "passive"))
      (node (ref "J5") (pin "1") (pinfunction "1_1") (pintype "passive"))
      (node (ref "J6") (pin "22") (pinfunction "22_22") (pintype "passive"))
      (node (ref "J8") (pin "3") (pinfunction "3_3") (pintype "passive"))
      (node (ref "J9") (pin "3") (pinfunction "3_3") (pintype "passive"))
      (node (ref "JP1") (pin "3") (pinfunction "3_3") (pintype "passive"))
      (node (ref "JP3") (pin "8") (pinfunction "8_8") (pintype "passive"))
      (node (ref "R3") (pin "2") (pinfunction "2_2") (pintype "passive"))
      (node (ref "U2") (pin "25") (pinfunction "A8_25") (pintype "bidirectional"))
      (node (ref "U2") (pin "28") (pinfunction "BC2_28") (pintype "bidirectional"))
      (node (ref "U2") (pin "40") (pinfunction "VCC_40") (pintype "power_in"))
      (node (ref "U3") (pin "28") (pinfunction "VCC_28") (pintype "power_in"))
      (node (ref "U4") (pin "20") (pinfunction "VCC_20") (pintype "power_in"))
      (node (ref "U5") (pin "1") (pinfunction "CLR_1") (pintype "input"))
      (node (ref "U5") (pin "4") (pinfunction "PRE_4") (pintype "input"))
      (node (ref "U6") (pin "20") (pinfunction "VCC_20") (pintype "power_in"))
      (node (ref "U9") (pin "3") (pinfunction "VCC_3") (pintype "power_in"))
      (node (ref "XC1") (pin "P$25") (pinfunction "X25_P$25") (pintype "bidirectional"))
    )
    (net (code "100") (name "unconnected-(JP3-Pad4)") (class "Default")
      (node (ref "JP3") (pin "4") (pinfunction "4_4") (pintype "passive"))
    )
    (net (code "101") (name "unconnected-(U2-TST1-Pad39)") (class "Default")
      (node (ref "U2") (pin "39") (pinfunction "TST1_39") (pintype "bidirectional"))
    )
    (net (code "102") (name "unconnected-(U2-TST2-Pad26)") (class "Default")
      (node (ref "U2") (pin "26") (pinfunction "TST2_26") (pintype "bidirectional"))
    )
    (net (code "103") (name "unconnected-(U5B-CLK-Pad11)") (class "Default")
      (node (ref "U5") (pin "11") (pinfunction "CLK_11") (pintype "input"))
    )
    (net (code "104") (name "unconnected-(U5B-CLR-Pad13)") (class "Default")
      (node (ref "U5") (pin "13") (pinfunction "CLR_13") (pintype "input"))
    )
    (net (code "105") (name "unconnected-(U5B-D-Pad12)") (class "Default")
      (node (ref "U5") (pin "12") (pinfunction "D_12") (pintype "input"))
    )
    (net (code "106") (name "unconnected-(U5B-PRE-Pad10)") (class "Default")
      (node (ref "U5") (pin "10") (pinfunction "PRE_10") (pintype "input"))
    )
    (net (code "107") (name "unconnected-(U5B-Q-Pad9)") (class "Default")
      (node (ref "U5") (pin "9") (pinfunction "Q_9") (pintype "output"))
    )
    (net (code "108") (name "unconnected-(U5B-~{Q}-Pad8)") (class "Default")
      (node (ref "U5") (pin "8") (pinfunction "~{Q}_8") (pintype "output"))
    )
    (net (code "109") (name "Φ") (class "Default")
      (node (ref "J6") (pin "14") (pinfunction "14_14") (pintype "passive"))
      (node (ref "U5") (pin "3") (pinfunction "CLK_3") (pintype "input"))
      (node (ref "XC1") (pin "P$8") (pinfunction "X8_P$8") (pintype "bidirectional"))
    )
  )
)
